# uart_to_usb.net
KiCad netlist of a schematic drawn in Altium Designer
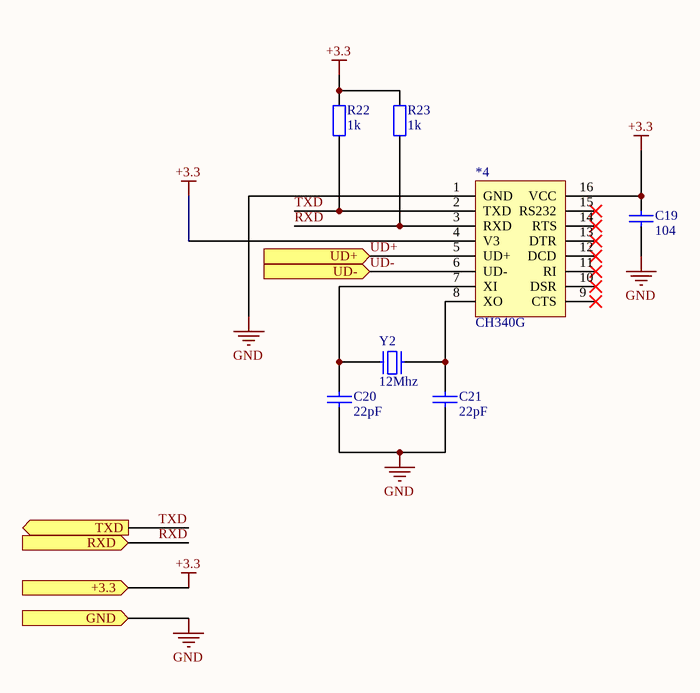
[diagram p0: uart_to_usb.SchDoc]

(export (version "E")
  (design (tool "Eeschema 10.0.6"))
  (components
    (comp (ref "*4") (value "CH340G") (footprint "CH340G") (libsource (lib "TrungVan_Lib") (part "CH340G")))
    (comp (ref "C19")
      (value "104")
      (footprint "tu 0603")
      (description "Dán")
      (libsource (lib "TrungVan_Lib") (part "Tu 0603 104 50V 10%"))
    )
    (comp (ref "C20")
      (value "22pF")
      (footprint "tu 0603")
      (description "Dán")
      (libsource (lib "TrungVan_Lib") (part "Tu 0603 22pF 50V 10%"))
    )
    (comp (ref "C21")
      (value "22pF")
      (footprint "tu 0603")
      (description "Dán")
      (libsource (lib "TrungVan_Lib") (part "Tu 0603 22pF 50V 10%"))
    )
    (comp (ref "R22")
      (value "1k")
      (footprint "tro smd 0805")
      (description "Dán")
      (libsource (lib "TrungVan_Lib") (part "Tro 0805 1% 1k"))
    )
    (comp (ref "R23")
      (value "1k")
      (footprint "tro smd 0805")
      (description "Dán")
      (libsource (lib "TrungVan_Lib") (part "Tro 0805 1% 1k"))
    )
    (comp (ref "Y2")
      (value "12Mhz")
      (footprint "Thach Anh 2 chan cam")
      (description "Crystal For all Crystal 2pin.")
      (libsource (lib "TrungVan_Lib") (part "Thach Anh 2 chan Cam"))
    )
  )
  (nets
    (net (code "1") (name "+3.3") (class "Default")
      (node (ref "*4") (pin "16") (pinfunction "VCC_16") (pintype "passive"))
      (node (ref "*4") (pin "4") (pinfunction "V3_4") (pintype "passive"))
      (node (ref "C19") (pin "1") (pinfunction "1_1") (pintype "passive"))
      (node (ref "R22") (pin "2") (pinfunction "2_2") (pintype "passive"))
      (node (ref "R23") (pin "2") (pinfunction "2_2") (pintype "passive"))
    )
    (net (code "2") (name "/RXD") (class "Default")
      (node (ref "*4") (pin "3") (pinfunction "RXD_3") (pintype "passive"))
      (node (ref "R23") (pin "1") (pinfunction "1_1") (pintype "passive"))
    )
    (net (code "3") (name "/TXD") (class "Default")
      (node (ref "*4") (pin "2") (pinfunction "TXD_2") (pintype "passive"))
      (node (ref "R22") (pin "1") (pinfunction "1_1") (pintype "passive"))
    )
    (net (code "4") (name "/UD+") (class "Default")
      (node (ref "*4") (pin "5") (pinfunction "UD+_5") (pintype "passive"))
    )
    (net (code "5") (name "/UD-") (class "Default")
      (node (ref "*4") (pin "6") (pinfunction "UD-_6") (pintype "passive"))
    )
    (net (code "6") (name "GND") (class "Default")
      (node (ref "*4") (pin "1") (pinfunction "GND_1") (pintype "passive"))
      (node (ref "C19") (pin "2") (pinfunction "2_2") (pintype "passive"))
      (node (ref "C20") (pin "2") (pinfunction "2_2") (pintype "passive"))
      (node (ref "C21") (pin "2") (pinfunction "2_2") (pintype "passive"))
    )
    (net (code "7") (name "Net-(*4-XI)") (class "Default")
      (node (ref "*4") (pin "7") (pinfunction "XI_7") (pintype "passive"))
      (node (ref "C20") (pin "1") (pinfunction "1_1") (pintype "passive"))
      (node (ref "Y2") (pin "1") (pinfunction "1_1") (pintype "passive"))
    )
    (net (code "8") (name "Net-(*4-XO)") (class "Default")
      (node (ref "*4") (pin "8") (pinfunction "XO_8") (pintype "passive"))
      (node (ref "C21") (pin "1") (pinfunction "1_1") (pintype "passive"))
      (node (ref "Y2") (pin "2") (pinfunction "2_2") (pintype "passive"))
    )
    (net (code "9") (name "unconnected-(*4-CTS-Pad9)") (class "Default")
      (node (ref "*4") (pin "9") (pinfunction "CTS_9") (pintype "passive+no_connect"))
    )
    (net (code "10") (name "unconnected-(*4-DCD-Pad12)") (class "Default")
      (node (ref "*4") (pin "12") (pinfunction "DCD_12") (pintype "passive+no_connect"))
    )
    (net (code "11") (name "unconnected-(*4-DSR-Pad10)") (class "Default")
      (node (ref "*4") (pin "10") (pinfunction "DSR_10") (pintype "passive+no_connect"))
    )
    (net (code "12") (name "unconnected-(*4-DTR-Pad13)") (class "Default")
      (node (ref "*4") (pin "13") (pinfunction "DTR_13") (pintype "passive+no_connect"))
    )
    (net (code "13") (name "unconnected-(*4-RI-Pad11)") (class "Default")
      (node (ref "*4") (pin "11") (pinfunction "RI_11") (pintype "passive+no_connect"))
    )
    (net (code "14") (name "unconnected-(*4-RS232-Pad15)") (class "Default")
      (node (ref "*4") (pin "15") (pinfunction "RS232_15") (pintype "passive+no_connect"))
    )
    (net (code "15") (name "unconnected-(*4-RTS-Pad14)") (class "Default")
      (node (ref "*4") (pin "14") (pinfunction "RTS_14") (pintype "passive+no_connect"))
    )
  )
)
